# powermeter_power_supply.net
KiCad netlist of a schematic drawn in Altium Designer
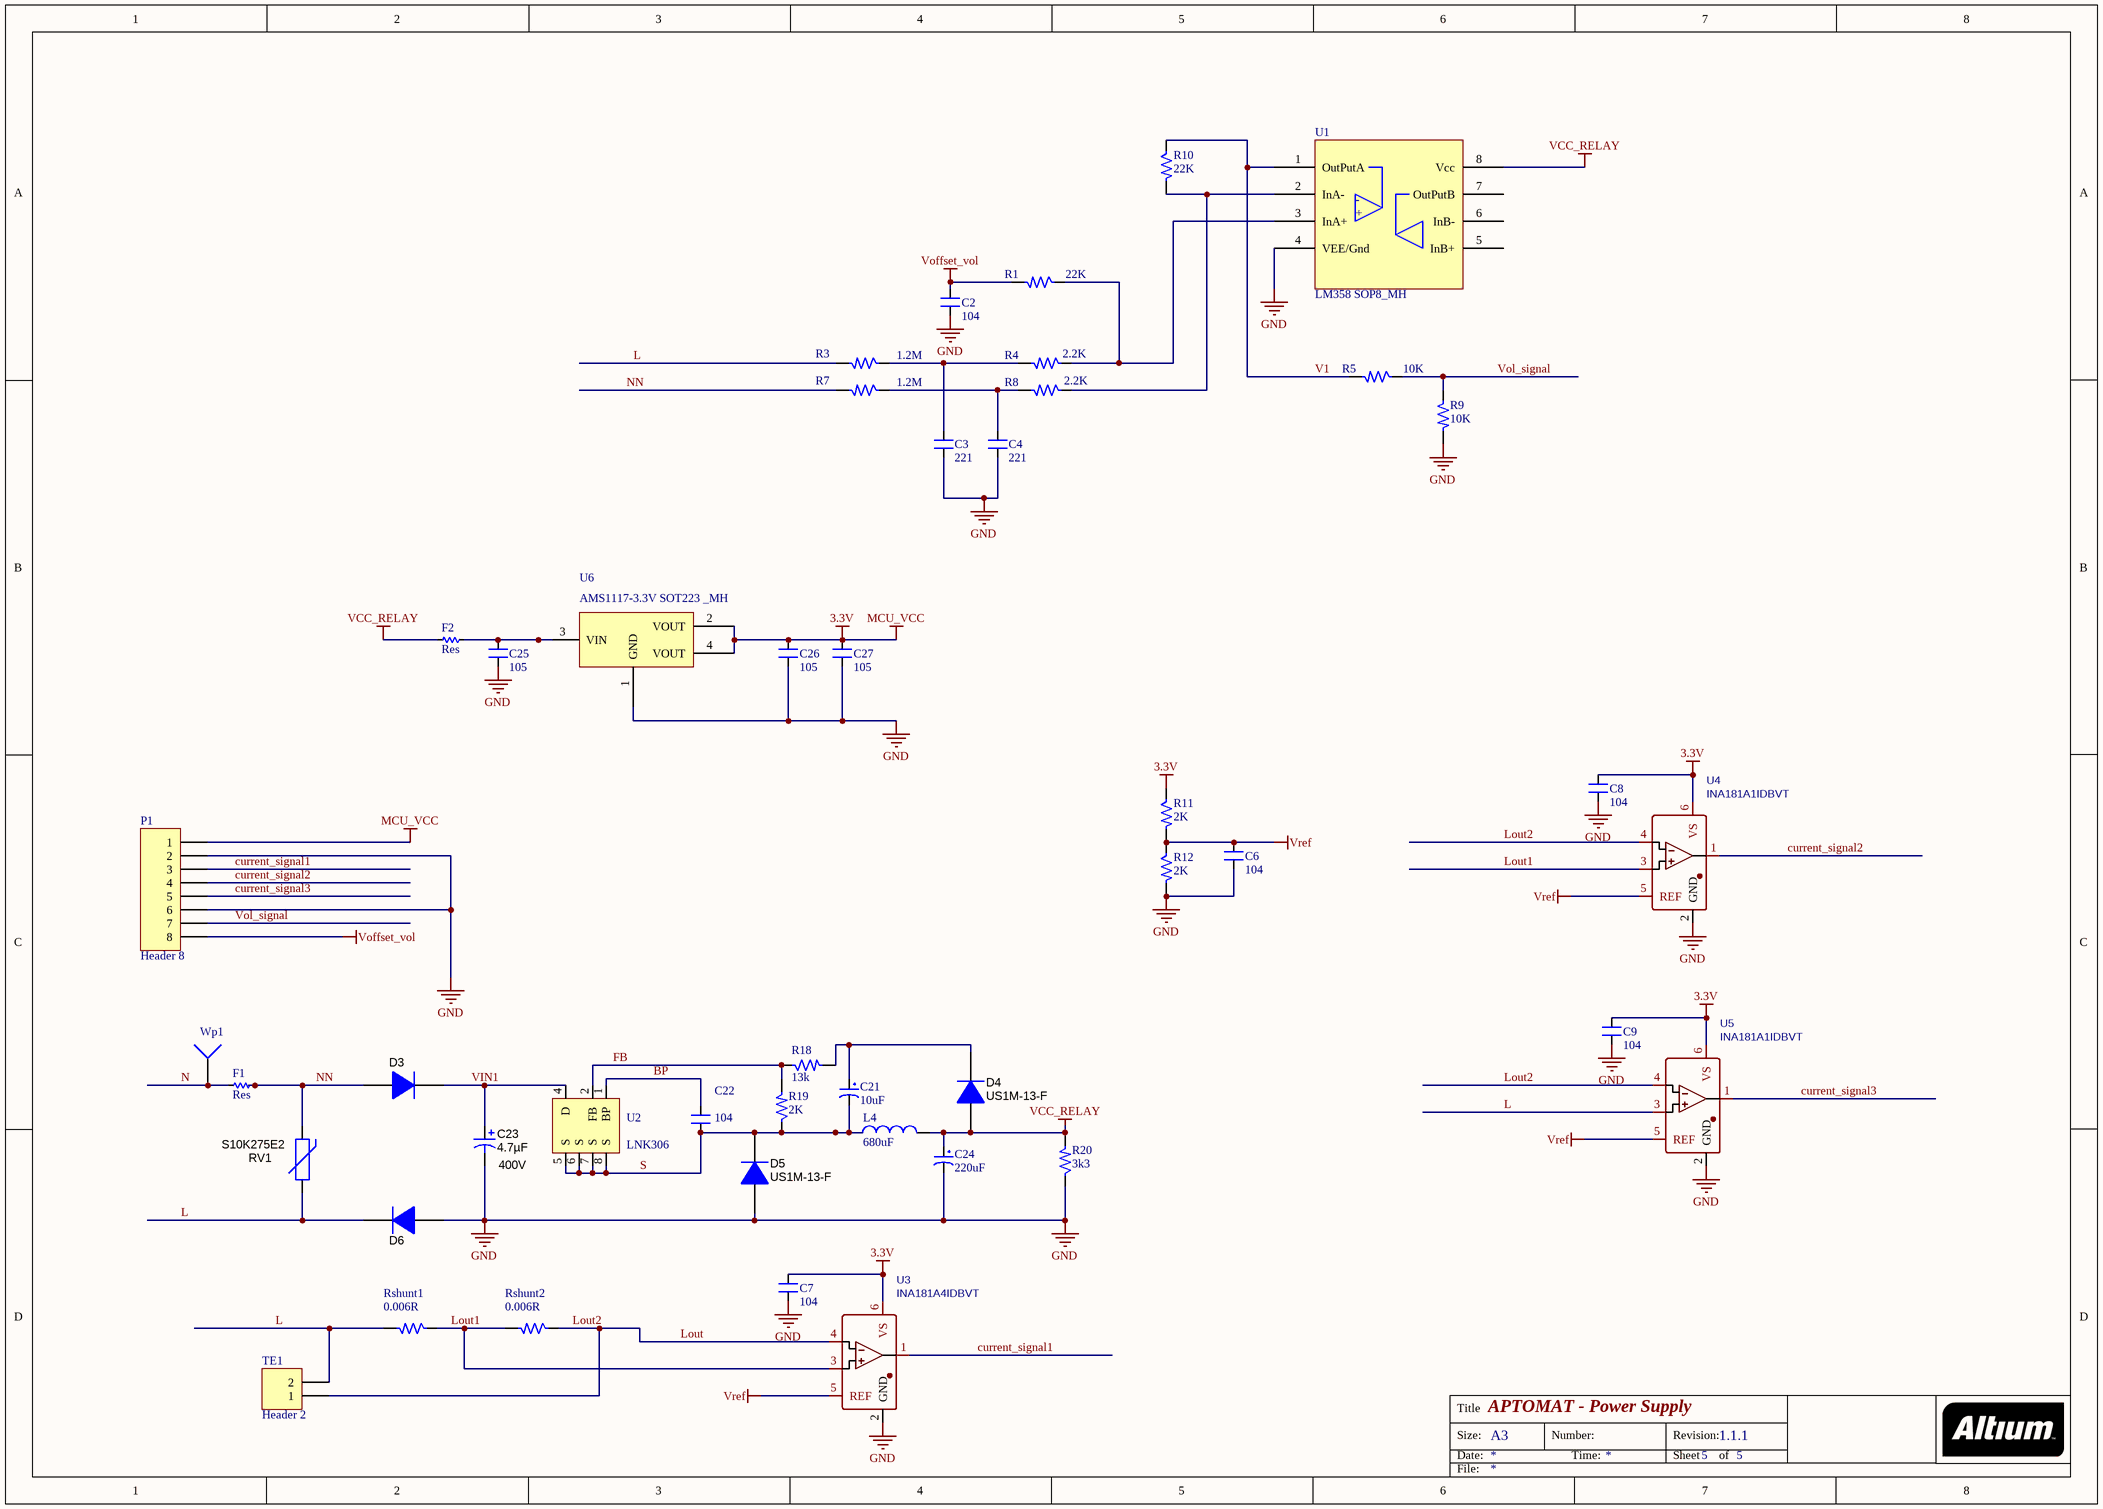
[diagram p0: powermeter_power_supply.SchDoc]

(export (version "E")
  (design (tool "Eeschema 10.0.6"))
  (components
    (comp (ref "C2")
      (value "104")
      (footprint "0805_HV")
      (description "Cap SMD")
      (libsource (lib "hatcatbietbay") (part "CM"))
    )
    (comp (ref "C3")
      (value "221")
      (footprint "0805_HV")
      (description "Cap SMD")
      (libsource (lib "hatcatbietbay") (part "CM"))
    )
    (comp (ref "C4")
      (value "221")
      (footprint "0805_HV")
      (description "Cap SMD")
      (libsource (lib "hatcatbietbay") (part "CM"))
    )
    (comp (ref "C6")
      (value "104")
      (footprint "0805_HV")
      (description "Cap SMD")
      (libsource (lib "hatcatbietbay") (part "CM"))
    )
    (comp (ref "C7")
      (value "104")
      (footprint "0805_HV")
      (description "Cap SMD")
      (libsource (lib "hatcatbietbay") (part "CM"))
    )
    (comp (ref "C8")
      (value "104")
      (footprint "0805_HV")
      (description "Cap SMD")
      (libsource (lib "hatcatbietbay") (part "CM"))
    )
    (comp (ref "C9")
      (value "104")
      (footprint "0805_HV")
      (description "Cap SMD")
      (libsource (lib "hatcatbietbay") (part "CM"))
    )
    (comp (ref "C21")
      (value "10uF")
      (footprint "TU_NHOM_10uF_MH")
      (description "TU_NHOM_10uF_25V_MH")
      (libsource (lib "MH_DA_THU_VIEN_16122016") (part "TU_NHOM_10uF_25V_MH"))
    )
    (comp (ref "C22")
      (value "104")
      (footprint "0805_HV")
      (description "Cap SMD")
      (libsource (lib "hatcatbietbay") (part "CM"))
    )
    (comp (ref "C23")
      (value "400AX6R8M8x11")
      (footprint "PcbLib1:PANACAP-G-GENERIC")
      (description "CAP, AL, 6.8uF, 400V, +/-20%, TH")
      (fields
        (field (name "VALUEDISPLAYED") "4.7µF")
        (field (name "MANUFACTURER") "Rubycon")
        (field (name "VALUE2") "400V")
        (field (name "PUBLISHER") "Texas Instruments")
      )
      (libsource (lib "Capacitor_Aluminum") (part "400AX6R8M8x11"))
    )
    (comp (ref "C24")
      (value "220uF")
      (footprint "TU_NHOM_2.5_MH")
      (description "TU_NHOM_220uF_25V_MH")
      (libsource (lib "MH_DA_THU_VIEN_16122016") (part "TU_NHOM_220uF_25V_MH"))
    )
    (comp (ref "C25")
      (value "105")
      (footprint "0805_HV")
      (description "Cap SMD")
      (libsource (lib "hatcatbietbay") (part "CM"))
    )
    (comp (ref "C26")
      (value "105")
      (footprint "0805_HV")
      (description "Cap SMD")
      (libsource (lib "hatcatbietbay") (part "CM"))
    )
    (comp (ref "C27")
      (value "105")
      (footprint "0805_HV")
      (description "Cap SMD")
      (libsource (lib "hatcatbietbay") (part "CM"))
    )
    (comp (ref "D3")
      (value "US1M-13-F")
      (footprint "PcbLib1:SMB")
      (description "Diode, Ultrafast, 600V, 1A, SMB")
      (fields (field (name "MANUFACTURER") "Diodes Inc.") (field (name "PUBLISHER") "Texas Instruments"))
      (libsource (lib "Diode") (part "MURS160-13-F"))
    )
    (comp (ref "D4")
      (value "US1M-13-F")
      (footprint "PcbLib1:SMB")
      (description "Diode, Ultrafast, 600V, 1A, SMB")
      (fields
        (field (name "PARTNUMBER") "US1M-13-F")
        (field (name "MANUFACTURER") "Diodes Inc.")
        (field (name "PUBLISHER") "Texas Instruments")
      )
      (libsource (lib "Diode") (part "MURS160-13-F"))
    )
    (comp (ref "D5")
      (value "US1M-13-F")
      (footprint "PcbLib1:SMB")
      (description "Diode, Ultrafast, 600V, 1A, SMB")
      (fields
        (field (name "PARTNUMBER") "US1M-13-F")
        (field (name "MANUFACTURER") "Diodes Inc.")
        (field (name "PUBLISHER") "Texas Instruments")
      )
      (libsource (lib "Diode") (part "MURS160-13-F"))
    )
    (comp (ref "D6")
      (value "US1M-13-F")
      (footprint "PcbLib1:SMB")
      (description "Diode, Ultrafast, 600V, 1A, SMB")
      (fields (field (name "MANUFACTURER") "Diodes Inc.") (field (name "PUBLISHER") "Texas Instruments"))
      (libsource (lib "Diode") (part "MURS160-13-F"))
    )
    (comp (ref "F1")
      (value "Res")
      (footprint "1206")
      (description "Resistor")
      (fields
        (field (name "MANUFACTURER") "Generic Components")
        (field (name "PUBLISHER") "Altium Hobart Technology Centre")
      )
      (libsource (lib "LIBRARY") (part "Res-SMD"))
    )
    (comp (ref "F2")
      (value "Res")
      (footprint "1206")
      (description "Resistor")
      (fields
        (field (name "MANUFACTURER") "Generic Components")
        (field (name "PUBLISHER") "Altium Hobart Technology Centre")
      )
      (libsource (lib "LIBRARY") (part "Res-SMD"))
    )
    (comp (ref "L4")
      (value "680uF")
      (footprint "Inductor 4.5x5")
      (libsource (lib "MH_DA_THU_VIEN_16122016") (part "Inductor 4.5x5_MH"))
    )
    (comp (ref "P1")
      (value "Header 8")
      (footprint "CON6_1.5D")
      (description "Header, 8-Pin")
      (fields (field (name "PUBLISHER") "Altium Limited"))
      (libsource (lib "Miscellaneous Connectors") (part "Header 8"))
    )
    (comp (ref "R1")
      (value "22K")
      (footprint "0805_HV")
      (description "Resistor 1/4W")
      (libsource (lib "hatcatbietbay") (part "R"))
    )
    (comp (ref "R3")
      (value "1.2M")
      (footprint "1206")
      (description "Resistor 1/4W")
      (libsource (lib "hatcatbietbay") (part "R"))
    )
    (comp (ref "R4")
      (value "2.2K")
      (footprint "0805_HV")
      (description "Resistor 1/4W")
      (libsource (lib "hatcatbietbay") (part "R"))
    )
    (comp (ref "R5")
      (value "10K")
      (footprint "0805_HV")
      (description "Resistor 1/4W")
      (libsource (lib "hatcatbietbay") (part "R"))
    )
    (comp (ref "R7")
      (value "1.2M")
      (footprint "1206")
      (description "Resistor 1/4W")
      (libsource (lib "hatcatbietbay") (part "R"))
    )
    (comp (ref "R8")
      (value "2.2K")
      (footprint "0805_HV")
      (description "Resistor 1/4W")
      (libsource (lib "hatcatbietbay") (part "R"))
    )
    (comp (ref "R9")
      (value "10K")
      (footprint "0805_HV")
      (description "Resistor 1/4W")
      (libsource (lib "hatcatbietbay") (part "R"))
    )
    (comp (ref "R10")
      (value "22K")
      (footprint "0805_HV")
      (description "Resistor 1/4W")
      (libsource (lib "hatcatbietbay") (part "R"))
    )
    (comp (ref "R11")
      (value "2K")
      (footprint "0805_HV")
      (description "Resistor 1/4W")
      (libsource (lib "hatcatbietbay") (part "R"))
    )
    (comp (ref "R12")
      (value "2K")
      (footprint "0805_HV")
      (description "Resistor 1/4W")
      (libsource (lib "hatcatbietbay") (part "R"))
    )
    (comp (ref "R18")
      (value "13k")
      (footprint "0805_HV")
      (description "Resistor 1/4W")
      (libsource (lib "hatcatbietbay") (part "R"))
    )
    (comp (ref "R19")
      (value "2K")
      (footprint "0805_HV")
      (description "Resistor 1/4W")
      (libsource (lib "hatcatbietbay") (part "R"))
    )
    (comp (ref "R20")
      (value "3k3")
      (footprint "0805_HV")
      (description "Resistor 1/4W")
      (libsource (lib "hatcatbietbay") (part "R"))
    )
    (comp (ref "Rshunt1")
      (value "0.006R")
      (footprint "RESC2728")
      (description "Resistor 1/4W")
      (libsource (lib "hatcatbietbay") (part "R"))
    )
    (comp (ref "Rshunt2")
      (value "0.006R")
      (footprint "RESC2728")
      (description "Resistor 1/4W")
      (libsource (lib "hatcatbietbay") (part "R"))
    )
    (comp (ref "RV1")
      (value "S10K275E2")
      (footprint "PcbLib1:VAR_S10K275E2")
      (description "Varistor 275V RMS 10MM Radial, TH")
      (fields
        (field (name "MANUFACTURER") "EPCOS Inc")
        (field (name "SYMBOLCREATOR") "a0412235")
        (field (name "PUBLISHER") "Texas Instruments")
      )
      (libsource (lib "Other_Passive") (part "S10K275E2"))
    )
    (comp (ref "TE1")
      (value "Header 2")
      (footprint "HDR1X2")
      (description "Header, 2-Pin")
      (fields (field (name "PUBLISHER") "Altium Limited"))
      (libsource (lib "Miscellaneous Connectors") (part "Header 2"))
    )
    (comp (ref "U1")
      (value "LM358 SOP8_MH")
      (footprint "SOP 8")
      (libsource (lib "MH_DA_THU_VIEN_16122016") (part "LM358 SOP8_MH"))
    )
    (comp (ref "U2") (value "LNK306") (footprint "SOP 7") (libsource (lib "LNK304") (part "Component_1")))
    (comp (ref "U3")
      (value "INA181A4IDBVT")
      (footprint "SOT95P280X145-6N")
      (fields
        (field (name "BOM_SUPPLIER PART") "C116200")
        (field (name "BOM_MANUFACTURER PART") "INA181A2IDBVT")
        (field (name "CONTRIBUTOR") "LCSC")
      )
      (libsource (lib "Schlib1") (part "INA181"))
    )
    (comp (ref "U4")
      (value "INA181A1IDBVT")
      (footprint "SOT95P280X145-6N")
      (fields
        (field (name "BOM_SUPPLIER PART") "C116200")
        (field (name "BOM_MANUFACTURER PART") "INA181A2IDBVT")
        (field (name "CONTRIBUTOR") "LCSC")
      )
      (libsource (lib "Schlib1") (part "INA181"))
    )
    (comp (ref "U5")
      (value "INA181A1IDBVT")
      (footprint "SOT95P280X145-6N")
      (fields
        (field (name "BOM_SUPPLIER PART") "C116200")
        (field (name "BOM_MANUFACTURER PART") "INA181A2IDBVT")
        (field (name "CONTRIBUTOR") "LCSC")
      )
      (libsource (lib "Schlib1") (part "INA181"))
    )
    (comp (ref "U6")
      (value "AMS1117-3.3V SOT223 _MH")
      (footprint "SOT223")
      (libsource (lib "MH_DA_THU_VIEN_16122016") (part "AMS1117-3.3V SOT223 _MH"))
    )
    (comp (ref "Wp1")
      (value "Socket")
      (footprint "PIN1")
      (fields (field (name "PUBLISHER") "Altium Limited"))
      (libsource (lib "Miscellaneous Connectors") (part "Socket"))
    )
  )
  (nets
    (net (code "1") (name "/BP") (class "Default")
      (node (ref "C22") (pin "2") (pinfunction "2_2") (pintype "passive"))
      (node (ref "U2") (pin "1") (pinfunction "BP_1") (pintype "passive"))
    )
    (net (code "2") (name "/FB") (class "Default")
      (node (ref "R18") (pin "1") (pinfunction "1_1") (pintype "passive"))
      (node (ref "R19") (pin "2") (pinfunction "2_2") (pintype "passive"))
      (node (ref "U2") (pin "2") (pinfunction "FB_2") (pintype "passive"))
    )
    (net (code "3") (name "/L") (class "Default")
      (node (ref "D6") (pin "1") (pinfunction "K_1") (pintype "passive"))
      (node (ref "R3") (pin "2") (pinfunction "2_2") (pintype "passive"))
      (node (ref "RV1") (pin "1") (pinfunction "1_1") (pintype "passive"))
      (node (ref "Rshunt1") (pin "2") (pinfunction "2_2") (pintype "passive"))
      (node (ref "TE1") (pin "2") (pinfunction "2_2") (pintype "passive"))
      (node (ref "U5") (pin "3") (pinfunction "IN+_3") (pintype "passive"))
    )
    (net (code "4") (name "/Lout") (class "Default")
      (node (ref "Rshunt2") (pin "1") (pinfunction "1_1") (pintype "passive"))
      (node (ref "TE1") (pin "1") (pinfunction "1_1") (pintype "passive"))
      (node (ref "U3") (pin "4") (pinfunction "IN-_4") (pintype "passive"))
      (node (ref "U4") (pin "4") (pinfunction "IN-_4") (pintype "passive"))
      (node (ref "U5") (pin "4") (pinfunction "IN-_4") (pintype "passive"))
    )
    (net (code "5") (name "/Lout1") (class "Default")
      (node (ref "Rshunt1") (pin "1") (pinfunction "1_1") (pintype "passive"))
      (node (ref "Rshunt2") (pin "2") (pinfunction "2_2") (pintype "passive"))
      (node (ref "U3") (pin "3") (pinfunction "IN+_3") (pintype "passive"))
      (node (ref "U4") (pin "3") (pinfunction "IN+_3") (pintype "passive"))
    )
    (net (code "6") (name "/N") (class "Default")
      (node (ref "F1") (pin "2") (pinfunction "2_2") (pintype "passive"))
      (node (ref "Wp1") (pin "1") (pinfunction "1_1") (pintype "passive"))
    )
    (net (code "7") (name "/NN") (class "Default")
      (node (ref "D3") (pin "2") (pinfunction "A_2") (pintype "passive"))
      (node (ref "F1") (pin "1") (pinfunction "1_1") (pintype "passive"))
      (node (ref "R7") (pin "2") (pinfunction "2_2") (pintype "passive"))
      (node (ref "RV1") (pin "2") (pinfunction "2_2") (pintype "passive"))
    )
    (net (code "8") (name "/S") (class "Default")
      (node (ref "C21") (pin "2") (pinfunction "2_2") (pintype "passive"))
      (node (ref "C22") (pin "1") (pinfunction "1_1") (pintype "passive"))
      (node (ref "D5") (pin "1") (pinfunction "K_1") (pintype "passive"))
      (node (ref "L4") (pin "1") (pinfunction "1_1") (pintype "passive"))
      (node (ref "R19") (pin "1") (pinfunction "1_1") (pintype "passive"))
      (node (ref "U2") (pin "5") (pinfunction "S_5") (pintype "passive"))
      (node (ref "U2") (pin "6") (pinfunction "S_6") (pintype "passive"))
      (node (ref "U2") (pin "7") (pinfunction "S_7") (pintype "passive"))
      (node (ref "U2") (pin "8") (pinfunction "S_8") (pintype "passive"))
    )
    (net (code "9") (name "/V1") (class "Default")
      (node (ref "R10") (pin "1") (pinfunction "1_1") (pintype "passive"))
      (node (ref "R5") (pin "2") (pinfunction "2_2") (pintype "passive"))
      (node (ref "U1") (pin "1") (pinfunction "OutPutA_1") (pintype "passive"))
    )
    (net (code "10") (name "/VIN1") (class "Default")
      (node (ref "C23") (pin "1") (pinfunction "+_1") (pintype "passive"))
      (node (ref "D3") (pin "1") (pinfunction "K_1") (pintype "passive"))
      (node (ref "U2") (pin "4") (pinfunction "D_4") (pintype "passive"))
    )
    (net (code "11") (name "/Vol_signal") (class "Default")
      (node (ref "P1") (pin "7") (pinfunction "7_7") (pintype "passive"))
      (node (ref "R5") (pin "1") (pinfunction "1_1") (pintype "passive"))
      (node (ref "R9") (pin "1") (pinfunction "1_1") (pintype "passive"))
    )
    (net (code "12") (name "/current_signal1") (class "Default")
      (node (ref "P1") (pin "3") (pinfunction "3_3") (pintype "passive"))
      (node (ref "U3") (pin "1") (pinfunction "OUT_1") (pintype "passive"))
    )
    (net (code "13") (name "/current_signal2") (class "Default")
      (node (ref "P1") (pin "4") (pinfunction "4_4") (pintype "passive"))
      (node (ref "U4") (pin "1") (pinfunction "OUT_1") (pintype "passive"))
    )
    (net (code "14") (name "/current_signal3") (class "Default")
      (node (ref "P1") (pin "5") (pinfunction "5_5") (pintype "passive"))
      (node (ref "U5") (pin "1") (pinfunction "OUT_1") (pintype "passive"))
    )
    (net (code "15") (name "3.3V") (class "Default")
      (node (ref "C26") (pin "2") (pinfunction "2_2") (pintype "passive"))
      (node (ref "C27") (pin "2") (pinfunction "2_2") (pintype "passive"))
      (node (ref "C7") (pin "2") (pinfunction "2_2") (pintype "passive"))
      (node (ref "C8") (pin "2") (pinfunction "2_2") (pintype "passive"))
      (node (ref "C9") (pin "2") (pinfunction "2_2") (pintype "passive"))
      (node (ref "P1") (pin "1") (pinfunction "1_1") (pintype "passive"))
      (node (ref "R11") (pin "1") (pinfunction "1_1") (pintype "passive"))
      (node (ref "U3") (pin "6") (pinfunction "VS_6") (pintype "passive"))
      (node (ref "U4") (pin "6") (pinfunction "VS_6") (pintype "passive"))
      (node (ref "U5") (pin "6") (pinfunction "VS_6") (pintype "passive"))
      (node (ref "U6") (pin "2") (pinfunction "VOUT_2") (pintype "passive"))
      (node (ref "U6") (pin "4") (pinfunction "VOUT_4") (pintype "passive"))
    )
    (net (code "16") (name "GND") (class "Default")
      (node (ref "C2") (pin "1") (pinfunction "1_1") (pintype "passive"))
      (node (ref "C23") (pin "2") (pinfunction "-_2") (pintype "passive"))
      (node (ref "C24") (pin "2") (pinfunction "2_2") (pintype "passive"))
      (node (ref "C25") (pin "1") (pinfunction "1_1") (pintype "passive"))
      (node (ref "C26") (pin "1") (pinfunction "1_1") (pintype "passive"))
      (node (ref "C27") (pin "1") (pinfunction "1_1") (pintype "passive"))
      (node (ref "C3") (pin "1") (pinfunction "1_1") (pintype "passive"))
      (node (ref "C4") (pin "1") (pinfunction "1_1") (pintype "passive"))
      (node (ref "C6") (pin "1") (pinfunction "1_1") (pintype "passive"))
      (node (ref "C7") (pin "1") (pinfunction "1_1") (pintype "passive"))
      (node (ref "C8") (pin "1") (pinfunction "1_1") (pintype "passive"))
      (node (ref "C9") (pin "1") (pinfunction "1_1") (pintype "passive"))
      (node (ref "D5") (pin "2") (pinfunction "A_2") (pintype "passive"))
      (node (ref "D6") (pin "2") (pinfunction "A_2") (pintype "passive"))
      (node (ref "P1") (pin "2") (pinfunction "2_2") (pintype "passive"))
      (node (ref "P1") (pin "6") (pinfunction "6_6") (pintype "passive"))
      (node (ref "R12") (pin "2") (pinfunction "2_2") (pintype "passive"))
      (node (ref "R20") (pin "1") (pinfunction "1_1") (pintype "passive"))
      (node (ref "R9") (pin "2") (pinfunction "2_2") (pintype "passive"))
      (node (ref "U1") (pin "4") (pinfunction "VEE/Gnd_4") (pintype "passive"))
      (node (ref "U3") (pin "2") (pinfunction "GND_2") (pintype "passive"))
      (node (ref "U4") (pin "2") (pinfunction "GND_2") (pintype "passive"))
      (node (ref "U5") (pin "2") (pinfunction "GND_2") (pintype "passive"))
      (node (ref "U6") (pin "1") (pinfunction "GND_1") (pintype "passive"))
    )
    (net (code "17") (name "Net-(C3-Pad2)") (class "Default")
      (node (ref "C3") (pin "2") (pinfunction "2_2") (pintype "passive"))
      (node (ref "R3") (pin "1") (pinfunction "1_1") (pintype "passive"))
      (node (ref "R4") (pin "2") (pinfunction "2_2") (pintype "passive"))
    )
    (net (code "18") (name "Net-(C4-Pad2)") (class "Default")
      (node (ref "C4") (pin "2") (pinfunction "2_2") (pintype "passive"))
      (node (ref "R7") (pin "1") (pinfunction "1_1") (pintype "passive"))
      (node (ref "R8") (pin "2") (pinfunction "2_2") (pintype "passive"))
    )
    (net (code "19") (name "Net-(D4-K)") (class "Default")
      (node (ref "C21") (pin "1") (pinfunction "1_1") (pintype "passive"))
      (node (ref "D4") (pin "1") (pinfunction "K_1") (pintype "passive"))
      (node (ref "R18") (pin "2") (pinfunction "2_2") (pintype "passive"))
    )
    (net (code "20") (name "Net-(U1-InA+)") (class "Default")
      (node (ref "R1") (pin "1") (pinfunction "1_1") (pintype "passive"))
      (node (ref "R4") (pin "1") (pinfunction "1_1") (pintype "passive"))
      (node (ref "U1") (pin "3") (pinfunction "InA+_3") (pintype "passive"))
    )
    (net (code "21") (name "Net-(U1-InA-)") (class "Default")
      (node (ref "R10") (pin "2") (pinfunction "2_2") (pintype "passive"))
      (node (ref "R8") (pin "1") (pinfunction "1_1") (pintype "passive"))
      (node (ref "U1") (pin "2") (pinfunction "InA-_2") (pintype "passive"))
    )
    (net (code "22") (name "Net-(U6-VIN)") (class "Default")
      (node (ref "C25") (pin "2") (pinfunction "2_2") (pintype "passive"))
      (node (ref "F2") (pin "1") (pinfunction "1_1") (pintype "passive"))
      (node (ref "U6") (pin "3") (pinfunction "VIN_3") (pintype "passive"))
    )
    (net (code "23") (name "VCC_RELAY") (class "Default")
      (node (ref "C24") (pin "1") (pinfunction "1_1") (pintype "passive"))
      (node (ref "D4") (pin "2") (pinfunction "A_2") (pintype "passive"))
      (node (ref "F2") (pin "2") (pinfunction "2_2") (pintype "passive"))
      (node (ref "L4") (pin "2") (pinfunction "2_2") (pintype "passive"))
      (node (ref "R20") (pin "2") (pinfunction "2_2") (pintype "passive"))
      (node (ref "U1") (pin "8") (pinfunction "Vcc_8") (pintype "passive"))
    )
    (net (code "24") (name "Voffset_vol") (class "Default")
      (node (ref "C2") (pin "2") (pinfunction "2_2") (pintype "passive"))
      (node (ref "P1") (pin "8") (pinfunction "8_8") (pintype "passive"))
      (node (ref "R1") (pin "2") (pinfunction "2_2") (pintype "passive"))
    )
    (net (code "25") (name "Vref") (class "Default")
      (node (ref "C6") (pin "2") (pinfunction "2_2") (pintype "passive"))
      (node (ref "R11") (pin "2") (pinfunction "2_2") (pintype "passive"))
      (node (ref "R12") (pin "1") (pinfunction "1_1") (pintype "passive"))
      (node (ref "U3") (pin "5") (pinfunction "REF_5") (pintype "passive"))
      (node (ref "U4") (pin "5") (pinfunction "REF_5") (pintype "passive"))
      (node (ref "U5") (pin "5") (pinfunction "REF_5") (pintype "passive"))
    )
    (net (code "26") (name "unconnected-(U1-InB+-Pad5)") (class "Default")
      (node (ref "U1") (pin "5") (pinfunction "InB+_5") (pintype "passive"))
    )
    (net (code "27") (name "unconnected-(U1-InB--Pad6)") (class "Default")
      (node (ref "U1") (pin "6") (pinfunction "InB-_6") (pintype "passive"))
    )
    (net (code "28") (name "unconnected-(U1-OutPutB-Pad7)") (class "Default")
      (node (ref "U1") (pin "7") (pinfunction "OutPutB_7") (pintype "passive"))
    )
  )
)
